# digibaro_v2.net
KiCad netlist of a schematic drawn in EAGLE
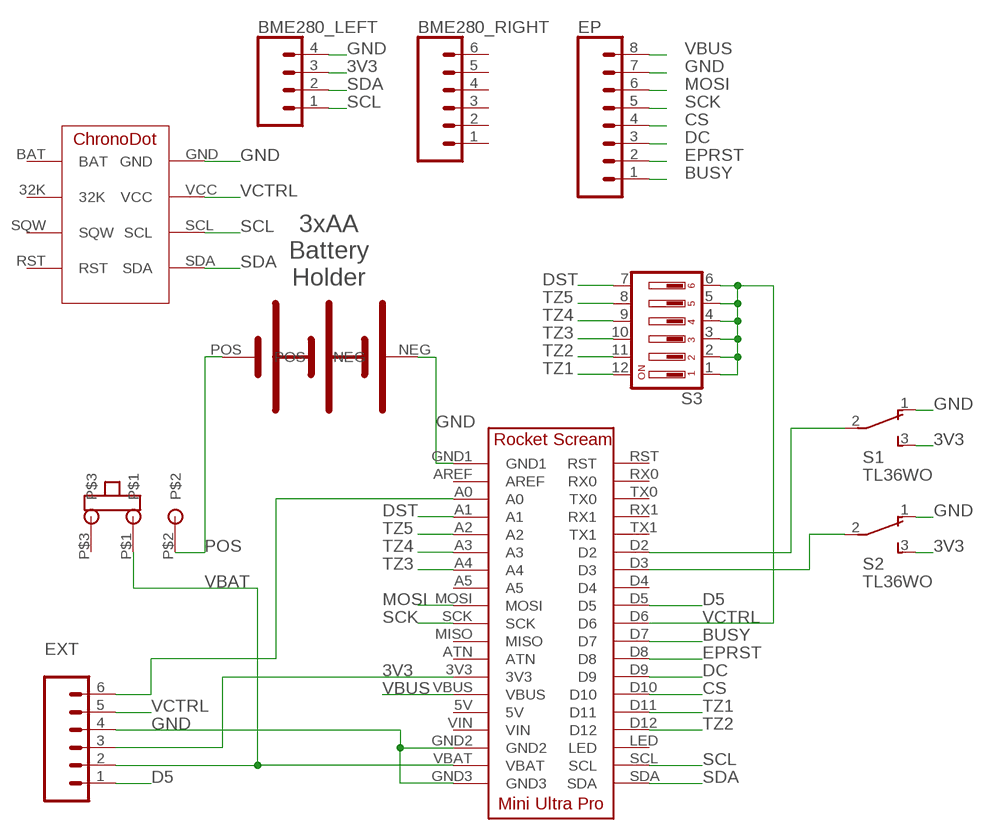
[diagram p0: schematic, sheet 1]

(export (version "E")
  (design (tool "Eeschema 10.0.6"))
  (components
    (comp (ref "BME280_LEFT")
      (value "CONN_04")
      (footprint "eagle-import:1X04")
      (libsource (lib "eagle-import") (part "CONN_04"))
    )
    (comp (ref "BME280_RIGHT")
      (value "CONN_06SILK_FEMALE_PTH")
      (footprint "eagle-import:1X06")
      (libsource (lib "eagle-import") (part "CONN_06SILK_FEMALE_PTH"))
    )
    (comp (ref "EP")
      (value "CONN_08\"")
      (footprint "eagle-import:1X08")
      (libsource (lib "eagle-import") (part "CONN_08{dblquote}"))
    )
    (comp (ref "EXT")
      (value "CONN_06SILK_FEMALE_PTH")
      (footprint "eagle-import:1X06")
      (libsource (lib "eagle-import") (part "CONN_06SILK_FEMALE_PTH"))
    )
    (comp (ref "S1")
      (value "TL36WO")
      (footprint "eagle-import:TL3XWO")
      (libsource (lib "eagle-import") (part "TL36WO"))
    )
    (comp (ref "S2")
      (value "TL36WO")
      (footprint "eagle-import:TL3XWO")
      (libsource (lib "eagle-import") (part "TL36WO"))
    )
    (comp (ref "S3")
      (value "DA06")
      (footprint "eagle-import:DA-06")
      (fields (field (name "MPN") "MCDA06"))
      (libsource (lib "eagle-import") (part "DA06"))
    )
    (comp (ref "U$1")
      (value "BATTERY-HOLDER_3AA")
      (footprint "eagle-import:BATTERY-HOLDER_3AA")
      (libsource (lib "eagle-import") (part "BATTERY-HOLDER_3AA"))
    )
    (comp (ref "U$2")
      (value "SLIDE-SWITCHNKKMINIATURE")
      (footprint "eagle-import:MS12ANG03")
      (libsource (lib "eagle-import") (part "SLIDE-SWITCHNKKMINIATURE"))
    )
    (comp (ref "U$3")
      (value "ULTRA-MINI-PRO")
      (footprint "eagle-import:ULTRA-MINI-PRO_RECEIVER")
      (libsource (lib "eagle-import") (part "ULTRA-MINI-PRO"))
    )
    (comp (ref "U$4")
      (value "CHRONODOT")
      (footprint "eagle-import:CHRONODOT_RECEIVER")
      (libsource (lib "eagle-import") (part "CHRONODOT"))
    )
  )
  (nets
    (net (code "1") (name "/3V3") (class "Default")
      (node (ref "BME280_LEFT") (pin "3") (pinfunction "3_3") (pintype "passive"))
      (node (ref "EXT") (pin "3") (pinfunction "3_3") (pintype "passive"))
      (node (ref "S1") (pin "3") (pinfunction "S_3") (pintype "passive"))
      (node (ref "S2") (pin "3") (pinfunction "S_3") (pintype "passive"))
      (node (ref "U$3") (pin "3V3") (pinfunction "3V3_3V3") (pintype "bidirectional"))
    )
    (net (code "2") (name "/BUSY") (class "Default")
      (node (ref "EP") (pin "1") (pinfunction "1_1") (pintype "passive"))
      (node (ref "U$3") (pin "D7") (pinfunction "D7_D7") (pintype "bidirectional"))
    )
    (net (code "3") (name "/CS") (class "Default")
      (node (ref "EP") (pin "4") (pinfunction "4_4") (pintype "passive"))
      (node (ref "U$3") (pin "D10") (pinfunction "D10_D10") (pintype "bidirectional"))
    )
    (net (code "4") (name "/D5") (class "Default")
      (node (ref "EXT") (pin "1") (pinfunction "1_1") (pintype "passive"))
      (node (ref "U$3") (pin "D5") (pinfunction "D5_D5") (pintype "bidirectional"))
    )
    (net (code "5") (name "/DC") (class "Default")
      (node (ref "EP") (pin "3") (pinfunction "3_3") (pintype "passive"))
      (node (ref "U$3") (pin "D9") (pinfunction "D9_D9") (pintype "bidirectional"))
    )
    (net (code "6") (name "/DST") (class "Default")
      (node (ref "S3") (pin "7") (pinfunction "7_7") (pintype "passive"))
      (node (ref "U$3") (pin "A1") (pinfunction "A1_A1") (pintype "bidirectional"))
    )
    (net (code "7") (name "/EPRST") (class "Default")
      (node (ref "EP") (pin "2") (pinfunction "2_2") (pintype "passive"))
      (node (ref "U$3") (pin "D8") (pinfunction "D8_D8") (pintype "bidirectional"))
    )
    (net (code "8") (name "/GND") (class "Default")
      (node (ref "BME280_LEFT") (pin "4") (pinfunction "4_4") (pintype "passive"))
      (node (ref "EP") (pin "7") (pinfunction "7_7") (pintype "passive"))
      (node (ref "EXT") (pin "4") (pinfunction "4_4") (pintype "passive"))
      (node (ref "S1") (pin "1") (pinfunction "O_1") (pintype "passive"))
      (node (ref "S2") (pin "1") (pinfunction "O_1") (pintype "passive"))
      (node (ref "U$1") (pin "NEG") (pinfunction "NEG_NEG") (pintype "bidirectional"))
      (node (ref "U$3") (pin "GND1") (pinfunction "GND1_GND1") (pintype "bidirectional"))
      (node (ref "U$3") (pin "GND2") (pinfunction "GND2_GND2") (pintype "bidirectional"))
      (node (ref "U$3") (pin "GND3") (pinfunction "GND3_GND3") (pintype "bidirectional"))
      (node (ref "U$4") (pin "GND") (pinfunction "GND_GND") (pintype "bidirectional"))
    )
    (net (code "9") (name "/MOSI") (class "Default")
      (node (ref "EP") (pin "6") (pinfunction "6_6") (pintype "passive"))
      (node (ref "U$3") (pin "MOSI") (pinfunction "MOSI_MOSI") (pintype "bidirectional"))
    )
    (net (code "10") (name "/POS") (class "Default")
      (node (ref "U$1") (pin "POS") (pinfunction "POS_POS") (pintype "bidirectional"))
      (node (ref "U$2") (pin "P$2") (pinfunction "P$2_P$2") (pintype "bidirectional"))
    )
    (net (code "11") (name "/SCK") (class "Default")
      (node (ref "EP") (pin "5") (pinfunction "5_5") (pintype "passive"))
      (node (ref "U$3") (pin "SCK") (pinfunction "SCK_SCK") (pintype "bidirectional"))
    )
    (net (code "12") (name "/SCL") (class "Default")
      (node (ref "BME280_LEFT") (pin "1") (pinfunction "1_1") (pintype "passive"))
      (node (ref "U$3") (pin "SCL") (pinfunction "SCL_SCL") (pintype "bidirectional"))
      (node (ref "U$4") (pin "SCL") (pinfunction "SCL_SCL") (pintype "bidirectional"))
    )
    (net (code "13") (name "/SDA") (class "Default")
      (node (ref "BME280_LEFT") (pin "2") (pinfunction "2_2") (pintype "passive"))
      (node (ref "U$3") (pin "SDA") (pinfunction "SDA_SDA") (pintype "bidirectional"))
      (node (ref "U$4") (pin "SDA") (pinfunction "SDA_SDA") (pintype "bidirectional"))
    )
    (net (code "14") (name "/TZ1") (class "Default")
      (node (ref "S3") (pin "12") (pinfunction "12_12") (pintype "passive"))
      (node (ref "U$3") (pin "D11") (pinfunction "D11_D11") (pintype "bidirectional"))
    )
    (net (code "15") (name "/TZ2") (class "Default")
      (node (ref "S3") (pin "11") (pinfunction "11_11") (pintype "passive"))
      (node (ref "U$3") (pin "D12") (pinfunction "D12_D12") (pintype "bidirectional"))
    )
    (net (code "16") (name "/TZ3") (class "Default")
      (node (ref "S3") (pin "10") (pinfunction "10_10") (pintype "passive"))
      (node (ref "U$3") (pin "A4") (pinfunction "A4_A4") (pintype "bidirectional"))
    )
    (net (code "17") (name "/TZ4") (class "Default")
      (node (ref "S3") (pin "9") (pinfunction "9_9") (pintype "passive"))
      (node (ref "U$3") (pin "A3") (pinfunction "A3_A3") (pintype "bidirectional"))
    )
    (net (code "18") (name "/TZ5") (class "Default")
      (node (ref "S3") (pin "8") (pinfunction "8_8") (pintype "passive"))
      (node (ref "U$3") (pin "A2") (pinfunction "A2_A2") (pintype "bidirectional"))
    )
    (net (code "19") (name "/VBAT") (class "Default")
      (node (ref "EXT") (pin "2") (pinfunction "2_2") (pintype "passive"))
      (node (ref "U$2") (pin "P$1") (pinfunction "P$1_P$1") (pintype "bidirectional"))
      (node (ref "U$3") (pin "VBAT") (pinfunction "VBAT_VBAT") (pintype "bidirectional"))
    )
    (net (code "20") (name "/VBUS") (class "Default")
      (node (ref "EP") (pin "8") (pinfunction "8_8") (pintype "passive"))
      (node (ref "U$3") (pin "VBUS") (pinfunction "VBUS_VBUS") (pintype "bidirectional"))
    )
    (net (code "21") (name "/VCTRL") (class "Default")
      (node (ref "EXT") (pin "5") (pinfunction "5_5") (pintype "passive"))
      (node (ref "S3") (pin "1") (pinfunction "1_1") (pintype "passive"))
      (node (ref "S3") (pin "2") (pinfunction "2_2") (pintype "passive"))
      (node (ref "S3") (pin "3") (pinfunction "3_3") (pintype "passive"))
      (node (ref "S3") (pin "4") (pinfunction "4_4") (pintype "passive"))
      (node (ref "S3") (pin "5") (pinfunction "5_5") (pintype "passive"))
      (node (ref "S3") (pin "6") (pinfunction "6_6") (pintype "passive"))
      (node (ref "U$3") (pin "D6") (pinfunction "D6_D6") (pintype "bidirectional"))
      (node (ref "U$4") (pin "VCC") (pinfunction "VCC_VCC") (pintype "bidirectional"))
    )
    (net (code "22") (name "Net-(EXT-Pad6)") (class "Default")
      (node (ref "EXT") (pin "6") (pinfunction "6_6") (pintype "passive"))
      (node (ref "U$3") (pin "A0") (pinfunction "A0_A0") (pintype "bidirectional"))
    )
    (net (code "23") (name "Net-(S1-P)") (class "Default")
      (node (ref "S1") (pin "2") (pinfunction "P_2") (pintype "passive"))
      (node (ref "U$3") (pin "D2") (pinfunction "D2_D2") (pintype "bidirectional"))
    )
    (net (code "24") (name "Net-(S2-P)") (class "Default")
      (node (ref "S2") (pin "2") (pinfunction "P_2") (pintype "passive"))
      (node (ref "U$3") (pin "D3") (pinfunction "D3_D3") (pintype "bidirectional"))
    )
    (net (code "25") (name "unconnected-(BME280_RIGHT-Pad1)") (class "Default")
      (node (ref "BME280_RIGHT") (pin "1") (pinfunction "1_1") (pintype "passive"))
    )
    (net (code "26") (name "unconnected-(BME280_RIGHT-Pad2)") (class "Default")
      (node (ref "BME280_RIGHT") (pin "2") (pinfunction "2_2") (pintype "passive"))
    )
    (net (code "27") (name "unconnected-(BME280_RIGHT-Pad3)") (class "Default")
      (node (ref "BME280_RIGHT") (pin "3") (pinfunction "3_3") (pintype "passive"))
    )
    (net (code "28") (name "unconnected-(BME280_RIGHT-Pad4)") (class "Default")
      (node (ref "BME280_RIGHT") (pin "4") (pinfunction "4_4") (pintype "passive"))
    )
    (net (code "29") (name "unconnected-(BME280_RIGHT-Pad5)") (class "Default")
      (node (ref "BME280_RIGHT") (pin "5") (pinfunction "5_5") (pintype "passive"))
    )
    (net (code "30") (name "unconnected-(BME280_RIGHT-Pad6)") (class "Default")
      (node (ref "BME280_RIGHT") (pin "6") (pinfunction "6_6") (pintype "passive"))
    )
    (net (code "31") (name "unconnected-(U$2-PadP$3)") (class "Default")
      (node (ref "U$2") (pin "P$3") (pinfunction "P$3_P$3") (pintype "bidirectional"))
    )
    (net (code "32") (name "unconnected-(U$3-Pad5V)") (class "Default")
      (node (ref "U$3") (pin "5V") (pinfunction "5V_5V") (pintype "bidirectional"))
    )
    (net (code "33") (name "unconnected-(U$3-PadA5)") (class "Default")
      (node (ref "U$3") (pin "A5") (pinfunction "A5_A5") (pintype "bidirectional"))
    )
    (net (code "34") (name "unconnected-(U$3-PadAREF)") (class "Default")
      (node (ref "U$3") (pin "AREF") (pinfunction "AREF_AREF") (pintype "bidirectional"))
    )
    (net (code "35") (name "unconnected-(U$3-PadATN)") (class "Default")
      (node (ref "U$3") (pin "ATN") (pinfunction "ATN_ATN") (pintype "bidirectional"))
    )
    (net (code "36") (name "unconnected-(U$3-PadD4)") (class "Default")
      (node (ref "U$3") (pin "D4") (pinfunction "D4_D4") (pintype "bidirectional"))
    )
    (net (code "37") (name "unconnected-(U$3-PadLED)") (class "Default")
      (node (ref "U$3") (pin "LED") (pinfunction "LED_LED") (pintype "bidirectional"))
    )
    (net (code "38") (name "unconnected-(U$3-PadMISO)") (class "Default")
      (node (ref "U$3") (pin "MISO") (pinfunction "MISO_MISO") (pintype "bidirectional"))
    )
    (net (code "39") (name "unconnected-(U$3-PadRST)") (class "Default")
      (node (ref "U$3") (pin "RST") (pinfunction "RST_RST") (pintype "bidirectional"))
    )
    (net (code "40") (name "unconnected-(U$3-PadRX0)") (class "Default")
      (node (ref "U$3") (pin "RX0") (pinfunction "RX0_RX0") (pintype "bidirectional"))
    )
    (net (code "41") (name "unconnected-(U$3-PadRX1)") (class "Default")
      (node (ref "U$3") (pin "RX1") (pinfunction "RX1_RX1") (pintype "bidirectional"))
    )
    (net (code "42") (name "unconnected-(U$3-PadTX0)") (class "Default")
      (node (ref "U$3") (pin "TX0") (pinfunction "TX0_TX0") (pintype "bidirectional"))
    )
    (net (code "43") (name "unconnected-(U$3-PadTX1)") (class "Default")
      (node (ref "U$3") (pin "TX1") (pinfunction "TX1_TX1") (pintype "bidirectional"))
    )
    (net (code "44") (name "unconnected-(U$3-PadVIN)") (class "Default")
      (node (ref "U$3") (pin "VIN") (pinfunction "VIN_VIN") (pintype "bidirectional"))
    )
    (net (code "45") (name "unconnected-(U$4-Pad32K)") (class "Default")
      (node (ref "U$4") (pin "32K") (pinfunction "32K_32K") (pintype "bidirectional"))
    )
    (net (code "46") (name "unconnected-(U$4-PadBAT)") (class "Default")
      (node (ref "U$4") (pin "BAT") (pinfunction "BAT_BAT") (pintype "bidirectional"))
    )
    (net (code "47") (name "unconnected-(U$4-PadRST)") (class "Default")
      (node (ref "U$4") (pin "RST") (pinfunction "RST_RST") (pintype "bidirectional"))
    )
    (net (code "48") (name "unconnected-(U$4-PadSQW)") (class "Default")
      (node (ref "U$4") (pin "SQW") (pinfunction "SQW_SQW") (pintype "bidirectional"))
    )
  )
)
